# Power_Section.net
KiCad netlist of a schematic drawn in Altium Designer
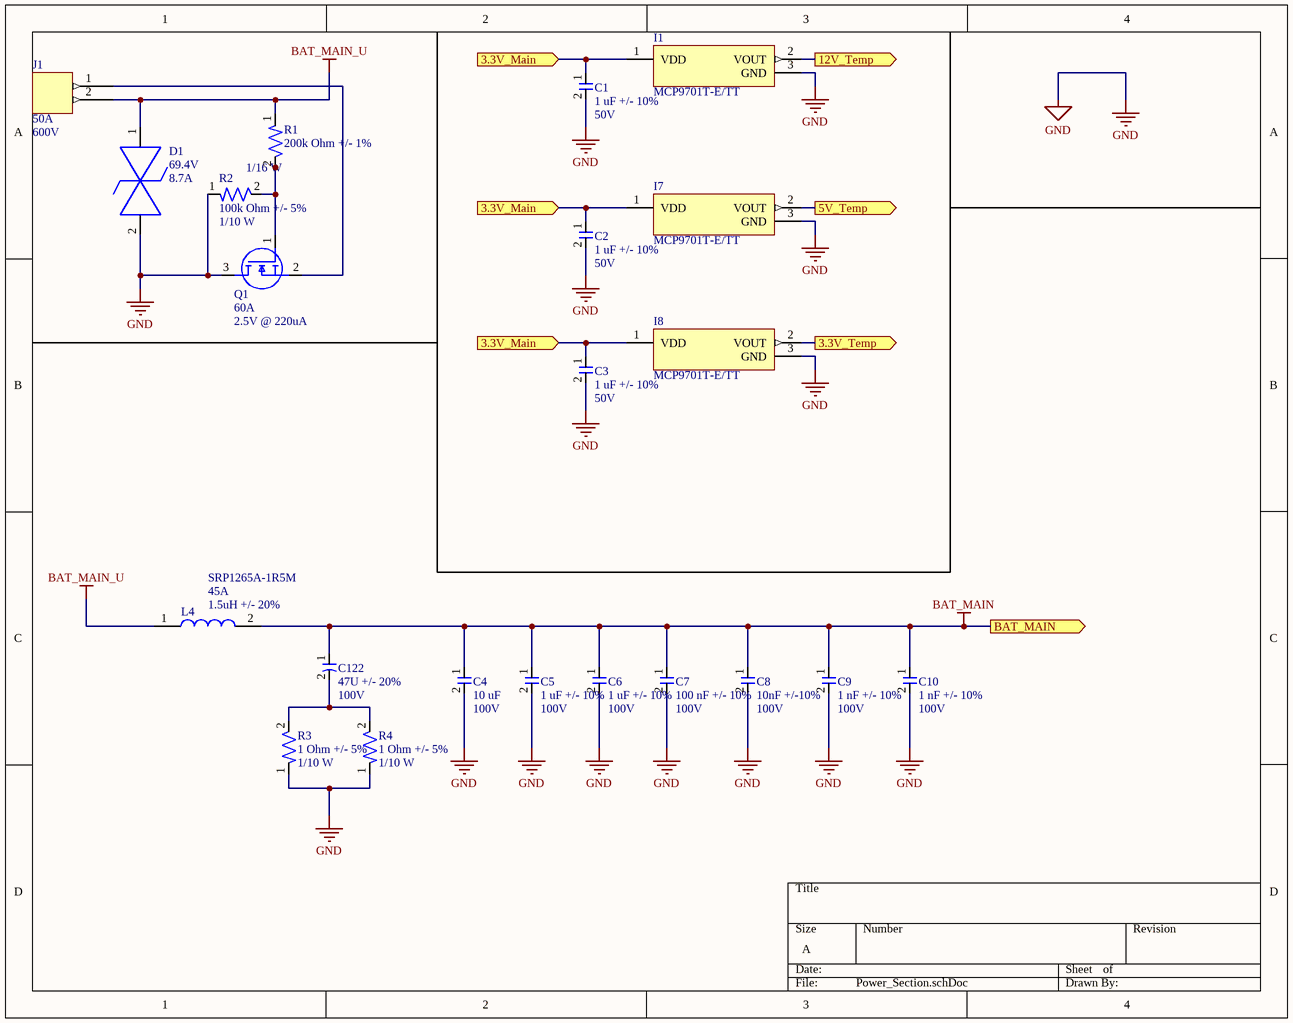
[diagram p0: Power_Section.schDoc]

(export (version "E")
  (design (tool "Eeschema 10.0.6"))
  (components
    (comp (ref "C1")
      (value "GCM21BR71H105KA03L")
      (footprint "CAP-0805")
      (description "50V 1uF X7R ±10% 0805 Multilayer Ceramic Capacitors MLCC - SMD/SMT ROHS")
      (fields
        (field (name "CAP") "1 uF +/- 10%")
        (field (name "VOLTAGE") "50V")
        (field (name "JLC PART NUMBER") "C126592")
      )
      (libsource (lib "MasterLib") (part "CAP-1U-0003-JLC"))
    )
    (comp (ref "C2")
      (value "GCM21BR71H105KA03L")
      (footprint "CAP-0805")
      (description "50V 1uF X7R ±10% 0805 Multilayer Ceramic Capacitors MLCC - SMD/SMT ROHS")
      (fields
        (field (name "CAP") "1 uF +/- 10%")
        (field (name "VOLTAGE") "50V")
        (field (name "JLC PART NUMBER") "C126592")
      )
      (libsource (lib "MasterLib") (part "CAP-1U-0003-JLC"))
    )
    (comp (ref "C3")
      (value "GCM21BR71H105KA03L")
      (footprint "CAP-0805")
      (description "50V 1uF X7R ±10% 0805 Multilayer Ceramic Capacitors MLCC - SMD/SMT ROHS")
      (fields
        (field (name "CAP") "1 uF +/- 10%")
        (field (name "VOLTAGE") "50V")
        (field (name "JLC PART NUMBER") "C126592")
      )
      (libsource (lib "MasterLib") (part "CAP-1U-0003-JLC"))
    )
    (comp (ref "C4")
      (value "GRM32EC72A106KE05L")
      (footprint "CAP-1210")
      (description "10 µF ±10% 100V Ceramic Capacitor X7S 1210 (3225 Metric)")
      (fields (field (name "CAPCITANCE") "10 uF") (field (name "VOLTAGE RATING") "100V"))
      (libsource (lib "MasterLib") (part "CAP-10U-0003"))
    )
    (comp (ref "C5")
      (value "C1206X105K101T")
      (footprint "CAP-1206 - duplicate")
      (description "100V 1uF X7R ±10% 1206 Multilayer Ceramic Capacitors MLCC - SMD/SMT ROHS")
      (fields
        (field (name "JLC PART NUMBER") "C106026")
        (field (name "CAPACITANCE") "1 uF +/- 10%")
        (field (name "VOLTAGE") "100V")
      )
      (libsource (lib "MasterLib") (part "CAP-1U-0004-JLC"))
    )
    (comp (ref "C6")
      (value "C1206X105K101T")
      (footprint "CAP-1206 - duplicate")
      (description "100V 1uF X7R ±10% 1206 Multilayer Ceramic Capacitors MLCC - SMD/SMT ROHS")
      (fields
        (field (name "JLC PART NUMBER") "C106026")
        (field (name "CAPACITANCE") "1 uF +/- 10%")
        (field (name "VOLTAGE") "100V")
      )
      (libsource (lib "MasterLib") (part "CAP-1U-0004-JLC"))
    )
    (comp (ref "C7")
      (value "CC0603KRX7R0BB104")
      (footprint "CAP-0603")
      (description "100V 100nF X7R ±10% 0603 Multilayer Ceramic Capacitors MLCC - SMD/SMT ROHS")
      (fields
        (field (name "JLC PART NUMBER") "C113803")
        (field (name "CAPACITANCE") "100 nF +/- 10%")
        (field (name "VOLTAGE") "100V")
      )
      (libsource (lib "MasterLib") (part "CAP-100N-0002-JLC"))
    )
    (comp (ref "C8")
      (value "CC0603KRX7R0BB103")
      (footprint "CAP-0603")
      (description "100V 10nF X7R ±10% 0603 Multilayer Ceramic Capacitors MLCC - SMD/SMT ROHS")
      (fields
        (field (name "MANUFACTURER") "Yageo")
        (field (name "JLC PART NUMBER") "C107059")
        (field (name "CAPACITANCE") "10nF +/-10%")
        (field (name "VOLTAGE RATING") "100V")
      )
      (libsource (lib "MasterLib") (part "CAP-10N-0003-JLC"))
    )
    (comp (ref "C9")
      (value "C0402C102K1GECAUTO")
      (footprint "CAP-0402")
      (description "100V 1nF C0G ±10% 0402 Multilayer Ceramic Capacitors MLCC - SMD/SMT ROHS")
      (fields
        (field (name "CAPACITANCE") "1 nF +/- 10%")
        (field (name "VOLTAGE") "100V")
        (field (name "JLC PART NUMBER") "C696348")
      )
      (libsource (lib "MasterLib") (part "CAP-1N-0004-JLC"))
    )
    (comp (ref "C10")
      (value "C0402C102K1GECAUTO")
      (footprint "CAP-0402")
      (description "100V 1nF C0G ±10% 0402 Multilayer Ceramic Capacitors MLCC - SMD/SMT ROHS")
      (fields
        (field (name "CAPACITANCE") "1 nF +/- 10%")
        (field (name "VOLTAGE") "100V")
        (field (name "JLC PART NUMBER") "C696348")
      )
      (libsource (lib "MasterLib") (part "CAP-1N-0004-JLC"))
    )
    (comp (ref "C122")
      (value "100SGV47M12.5X13.5")
      (footprint "ELEC-47U-0001")
      (description "47 µF 100 V Aluminum Electrolytic Capacitors Radial, Can - SMD 2000 Hrs @ 105°C")
      (fields (field (name "CAPACITANCE") "47U +/- 20%") (field (name "VOLTAGE") "100V"))
      (libsource (lib "MasterLib") (part "ELEC-47U-0001"))
    )
    (comp (ref "D1")
      (value "SMBJE43CAH")
      (footprint "DO-214AA (SMBJ)")
      (description "69.4V Clamp 8.7A Ipp Tvs Diode Surface Mount DO-214AA (SMBJ)")
      (fields (field (name "VCLAMP") "69.4V") (field (name "PEAK PULSER CURRENT") "8.7A"))
      (libsource (lib "MasterLib") (part "DIO-69.4V-0001"))
    )
    (comp (ref "I1")
      (value "MCP9701T-E/TT")
      (footprint "IC-TEMP-0001")
      (description "Temperature Sensor Analog, Local -10°C ~ 125°C 19.5mV/°C SOT-23-3")
      (fields (field (name "MANUFACTURER") "Microchip Technology"))
      (libsource (lib "MasterLib") (part "IC-TEMP-0001"))
    )
    (comp (ref "I7")
      (value "MCP9701T-E/TT")
      (footprint "IC-TEMP-0001")
      (description "Temperature Sensor Analog, Local -10°C ~ 125°C 19.5mV/°C SOT-23-3")
      (fields (field (name "MANUFACTURER") "Microchip Technology"))
      (libsource (lib "MasterLib") (part "IC-TEMP-0001"))
    )
    (comp (ref "I8")
      (value "MCP9701T-E/TT")
      (footprint "IC-TEMP-0001")
      (description "Temperature Sensor Analog, Local -10°C ~ 125°C 19.5mV/°C SOT-23-3")
      (fields (field (name "MANUFACTURER") "Microchip Technology"))
      (libsource (lib "MasterLib") (part "IC-TEMP-0001"))
    )
    (comp (ref "J1")
      (value "0389690002")
      (footprint "CON-2POS-0002")
      (description "2 Circuit 0.500\" (12.70mm) Barrier Block Connector Screws with Captive Plate")
      (fields (field (name "CURRENT") "50A") (field (name "VOLTAGE") "600V"))
      (libsource (lib "MasterLib") (part "CON-2POS-0002"))
    )
    (comp (ref "L4")
      (value "SRP1265A-1R5M")
      (footprint "PWRIND-1.5U-0002")
      (description "1.5 µH Shielded Drum Core, Wirewound Inductor 27 A 3mOhm Max Nonstandard")
      (fields
        (field (name "MANUFACTURER") "Bourns Electronics")
        (field (name "SATURATION CURRENT") "45A")
        (field (name "INDUCTANCE") "1.5uH +/- 20%")
        (field (name "COPYRIGHT") "Copyright (C) 2022 Ultra Librarian. All rights reserved.")
      )
      (libsource (lib "MasterLib") (part "PWRIND-1.5U-0002"))
    )
    (comp (ref "Q1")
      (value "TPH7R006PL,L1Q")
      (footprint "NMOS-8PowerVDFN")
      (description "N-Channel 60 V 60A (Tc) 81W (Tc) Surface Mount 8-SOP Advance (5x5)")
      (fields (field (name "DRAIN CURRENT") "60A") (field (name "VGS") "2.5V @ 220uA"))
      (libsource (lib "MasterLib") (part "NMOS-60A-0001"))
    )
    (comp (ref "R1")
      (value "RC-02W2003FT")
      (footprint "RES-0402")
      (description "62.5mW 50V ±1% ±200ppm/℃ -55℃~+155℃ 200kΩ 0402  Chip Resistor - Surface Mount ROHS")
      (fields
        (field (name "RESISTANCE") "200k Ohm +/- 1%")
        (field (name "JLC PART NUMBER") "C258094")
        (field (name "POWER") "1/16 W")
      )
      (libsource (lib "MasterLib") (part "RES-200K-0002-JLC"))
    )
    (comp (ref "R2")
      (value "ERJ2GEJ104X")
      (footprint "RES-0402")
      (description "100mW Thick Film Resistors ±5% ±200ppm/℃ -55℃~+155℃ 100kΩ 0402  Chip Resistor - Surface Mount ROHS")
      (fields
        (field (name "RESISTANCE") "100k Ohm +/- 5%")
        (field (name "POWER") "1/10 W")
        (field (name "JLC PART NUMBER") "C413017")
      )
      (libsource (lib "MasterLib") (part "RES-100K-0002-JLC"))
    )
    (comp (ref "R3")
      (value "ERJ2GEJ1R0X")
      (footprint "RES-0402")
      (fields
        (field (name "RESISTANVCE") "1 Ohm +/- 5%")
        (field (name "POWER") "1/10 W")
        (field (name "JLC PART NUMBER") "C412890")
      )
      (libsource (lib "MasterLib") (part "RES-1-0002-JLC"))
    )
    (comp (ref "R4")
      (value "ERJ2GEJ1R0X")
      (footprint "RES-0402")
      (fields
        (field (name "RESISTANVCE") "1 Ohm +/- 5%")
        (field (name "POWER") "1/10 W")
        (field (name "JLC PART NUMBER") "C412890")
      )
      (libsource (lib "MasterLib") (part "RES-1-0002-JLC"))
    )
  )
  (nets
    (net (code "1") (name "/3.3V_Main") (class "Default")
      (node (ref "C1") (pin "1") (pinfunction "1_1") (pintype "passive"))
      (node (ref "C2") (pin "1") (pinfunction "1_1") (pintype "passive"))
      (node (ref "C3") (pin "1") (pinfunction "1_1") (pintype "passive"))
      (node (ref "I1") (pin "1") (pinfunction "VDD_1") (pintype "power_in"))
      (node (ref "I7") (pin "1") (pinfunction "VDD_1") (pintype "power_in"))
      (node (ref "I8") (pin "1") (pinfunction "VDD_1") (pintype "power_in"))
    )
    (net (code "2") (name "/3.3V_Temp") (class "Default")
      (node (ref "I8") (pin "2") (pinfunction "VOUT_2") (pintype "output"))
    )
    (net (code "3") (name "/5V_Temp") (class "Default")
      (node (ref "I7") (pin "2") (pinfunction "VOUT_2") (pintype "output"))
    )
    (net (code "4") (name "/12V_Temp") (class "Default")
      (node (ref "I1") (pin "2") (pinfunction "VOUT_2") (pintype "output"))
    )
    (net (code "5") (name "BAT_MAIN") (class "Default")
      (node (ref "C10") (pin "1") (pinfunction "1_1") (pintype "passive"))
      (node (ref "C122") (pin "1") (pinfunction "1_1") (pintype "passive"))
      (node (ref "C4") (pin "1") (pinfunction "1_1") (pintype "passive"))
      (node (ref "C5") (pin "1") (pinfunction "1_1") (pintype "passive"))
      (node (ref "C6") (pin "1") (pinfunction "1_1") (pintype "passive"))
      (node (ref "C7") (pin "1") (pinfunction "1_1") (pintype "passive"))
      (node (ref "C8") (pin "1") (pinfunction "1_1") (pintype "passive"))
      (node (ref "C9") (pin "1") (pinfunction "1_1") (pintype "passive"))
      (node (ref "L4") (pin "2") (pinfunction "2_2") (pintype "passive"))
    )
    (net (code "6") (name "BAT_MAIN_U") (class "Default")
      (node (ref "D1") (pin "1") (pintype "passive"))
      (node (ref "J1") (pin "2") (pintype "output"))
      (node (ref "L4") (pin "1") (pinfunction "1_1") (pintype "passive"))
      (node (ref "R1") (pin "1") (pinfunction "1_1") (pintype "passive"))
    )
    (net (code "7") (name "GND") (class "Default")
      (node (ref "C1") (pin "2") (pinfunction "2_2") (pintype "passive"))
      (node (ref "C10") (pin "2") (pinfunction "2_2") (pintype "passive"))
      (node (ref "C2") (pin "2") (pinfunction "2_2") (pintype "passive"))
      (node (ref "C3") (pin "2") (pinfunction "2_2") (pintype "passive"))
      (node (ref "C4") (pin "2") (pinfunction "2_2") (pintype "passive"))
      (node (ref "C5") (pin "2") (pinfunction "2_2") (pintype "passive"))
      (node (ref "C6") (pin "2") (pinfunction "2_2") (pintype "passive"))
      (node (ref "C7") (pin "2") (pinfunction "2_2") (pintype "passive"))
      (node (ref "C8") (pin "2") (pinfunction "2_2") (pintype "passive"))
      (node (ref "C9") (pin "2") (pinfunction "2_2") (pintype "passive"))
      (node (ref "D1") (pin "2") (pintype "passive"))
      (node (ref "I1") (pin "3") (pinfunction "GND_3") (pintype "power_in"))
      (node (ref "I7") (pin "3") (pinfunction "GND_3") (pintype "power_in"))
      (node (ref "I8") (pin "3") (pinfunction "GND_3") (pintype "power_in"))
      (node (ref "Q1") (pin "3") (pinfunction "D_3") (pintype "passive"))
      (node (ref "R2") (pin "1") (pinfunction "1_1") (pintype "passive"))
      (node (ref "R3") (pin "1") (pinfunction "1_1") (pintype "passive"))
      (node (ref "R4") (pin "1") (pinfunction "1_1") (pintype "passive"))
    )
    (net (code "8") (name "Net-(C122-Pad2)") (class "Default")
      (node (ref "C122") (pin "2") (pinfunction "2_2") (pintype "passive"))
      (node (ref "R3") (pin "2") (pinfunction "2_2") (pintype "passive"))
      (node (ref "R4") (pin "2") (pinfunction "2_2") (pintype "passive"))
    )
    (net (code "9") (name "Net-(Q1-G)") (class "Default")
      (node (ref "Q1") (pin "1") (pinfunction "G_1") (pintype "passive"))
      (node (ref "R1") (pin "2") (pinfunction "2_2") (pintype "passive"))
      (node (ref "R2") (pin "2") (pinfunction "2_2") (pintype "passive"))
    )
    (net (code "10") (name "Net-(Q1-S)") (class "Default")
      (node (ref "J1") (pin "1") (pintype "output"))
      (node (ref "Q1") (pin "2") (pinfunction "S_2") (pintype "passive"))
    )
  )
)
